# schematic.net
KiCad netlist of a schematic drawn in EAGLE
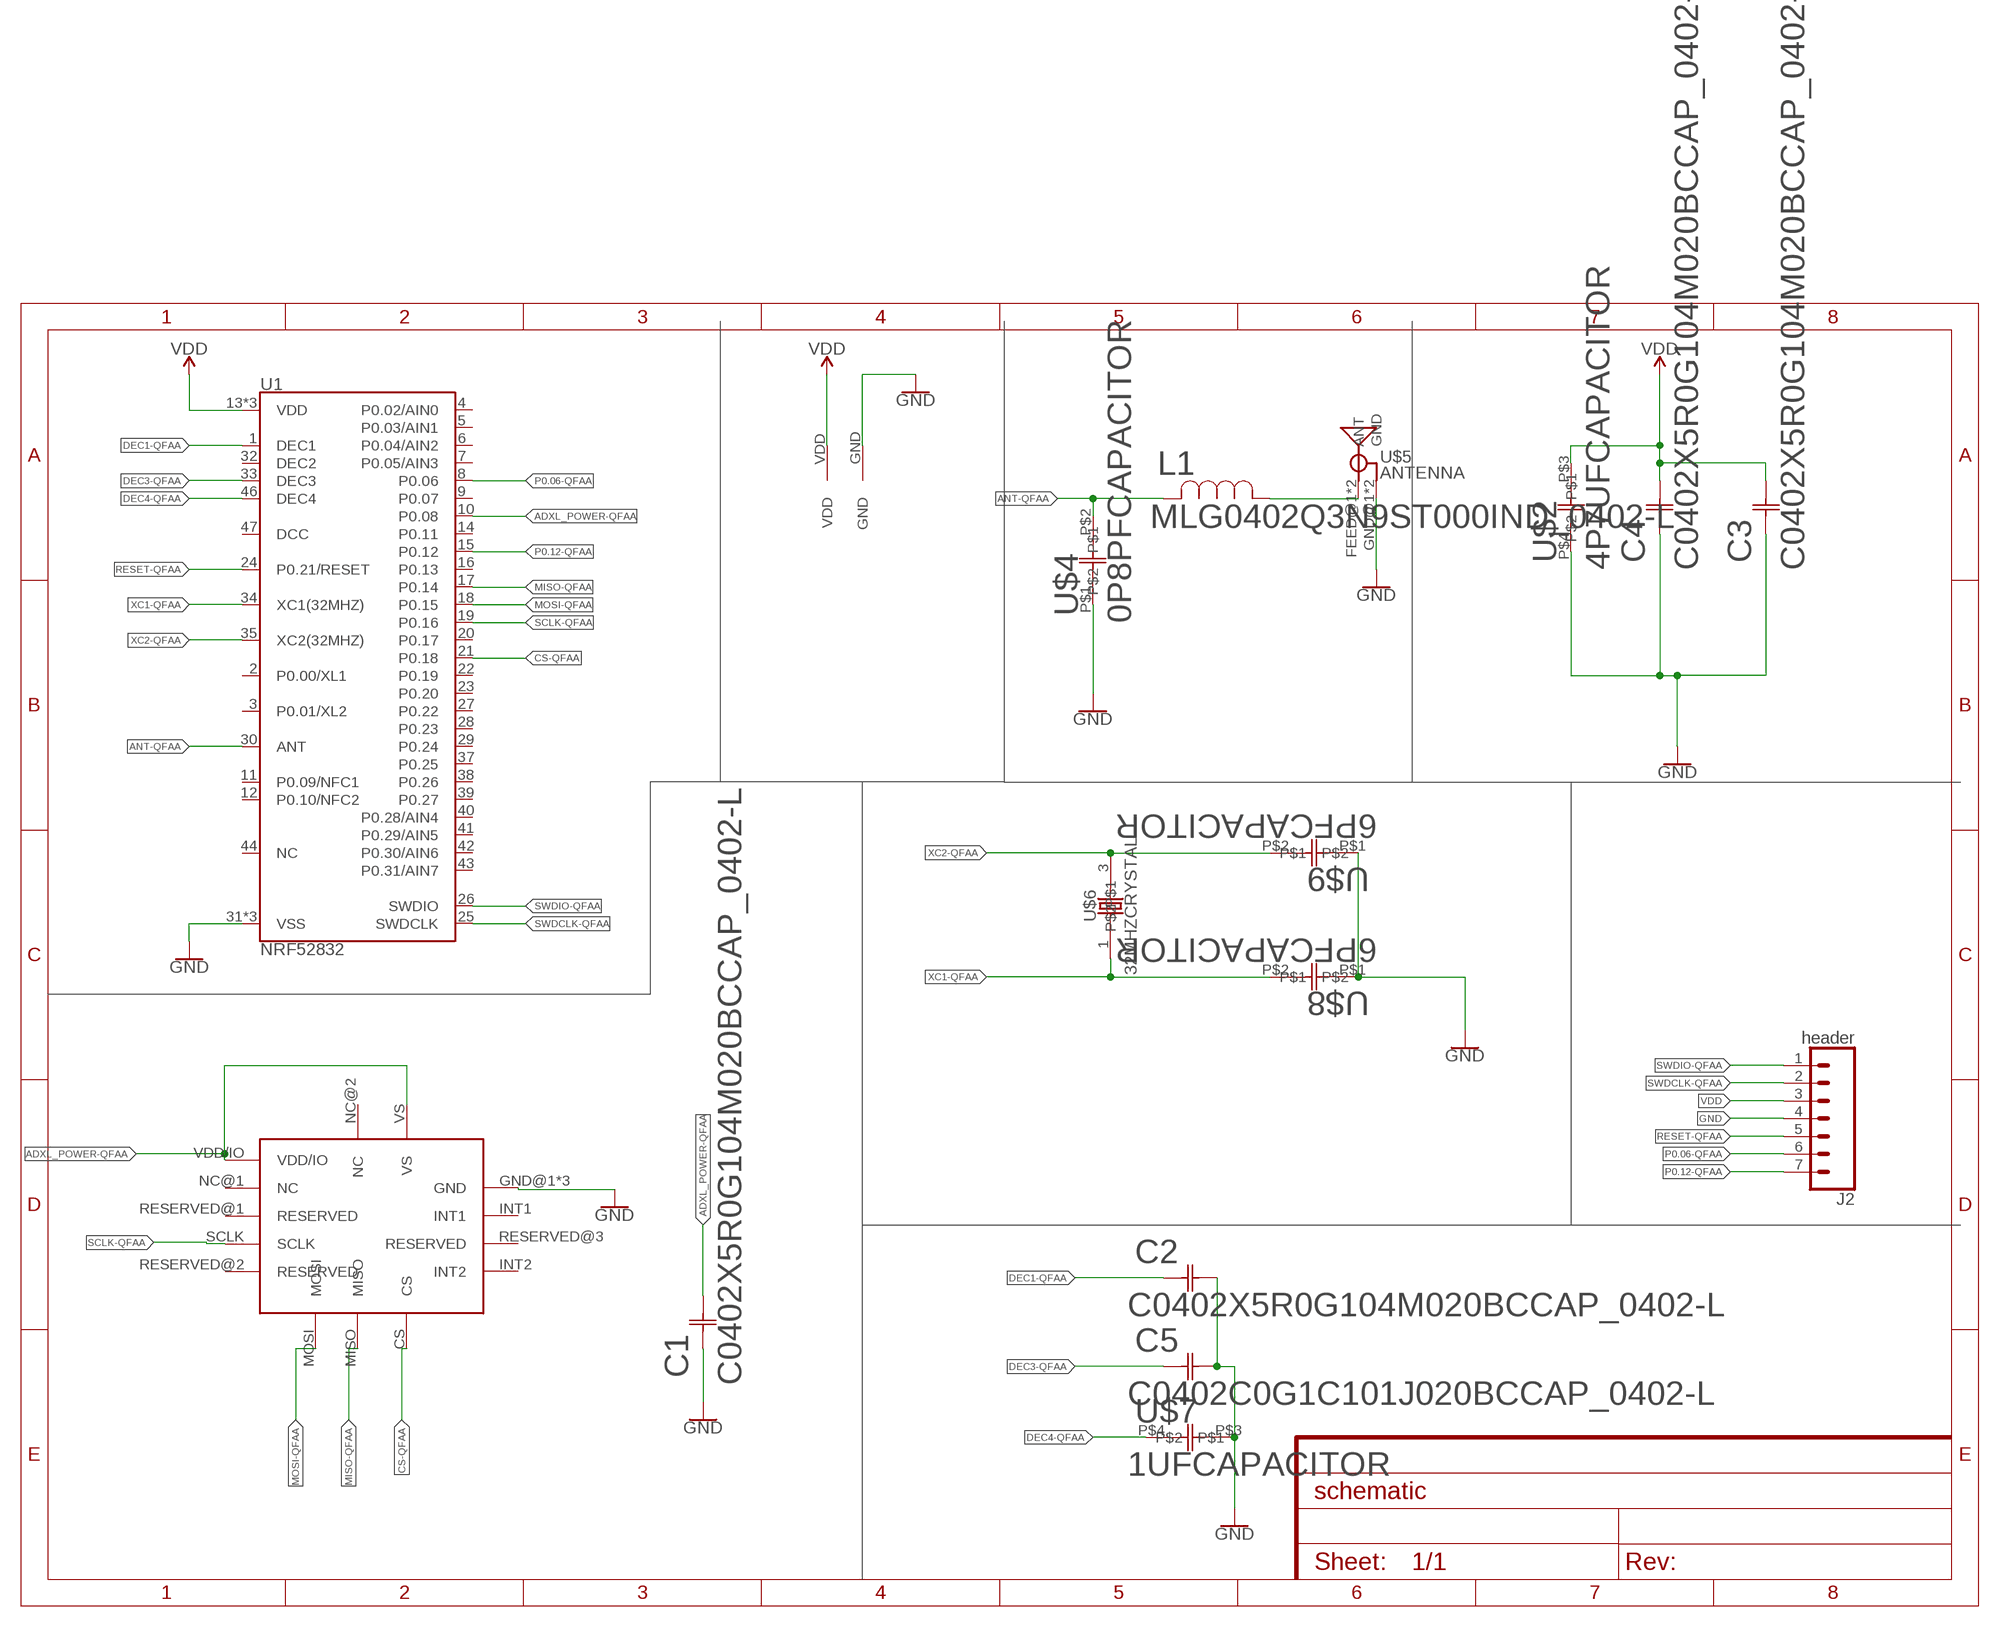
[diagram p0: schematic, sheet 1]

(export (version "E")
  (design (tool "Eeschema 10.0.6"))
  (components
    (comp (ref "C1")
      (value "C0402X5R0G104M020BCCAP_0402-L")
      (footprint "eagle-import:CAP_0402-L")
      (fields (field (name "MANUFACTURER_PART_NUMBER") "C0402C0G1C101J020BC"))
      (libsource (lib "eagle-import") (part "C0402X5R0G104M020BCCAP_0402-L"))
    )
    (comp (ref "C2")
      (value "C0402X5R0G104M020BCCAP_0402-L")
      (footprint "eagle-import:CAP_0402-L")
      (fields (field (name "MANUFACTURER_PART_NUMBER") "C0402C0G1C101J020BC"))
      (libsource (lib "eagle-import") (part "C0402X5R0G104M020BCCAP_0402-L"))
    )
    (comp (ref "C3")
      (value "C0402X5R0G104M020BCCAP_0402-L")
      (footprint "eagle-import:CAP_0402-L")
      (fields (field (name "MANUFACTURER_PART_NUMBER") "C0402C0G1C101J020BC"))
      (libsource (lib "eagle-import") (part "C0402X5R0G104M020BCCAP_0402-L"))
    )
    (comp (ref "C4")
      (value "C0402X5R0G104M020BCCAP_0402-L")
      (footprint "eagle-import:CAP_0402-L")
      (fields (field (name "MANUFACTURER_PART_NUMBER") "C0402C0G1C101J020BC"))
      (libsource (lib "eagle-import") (part "C0402X5R0G104M020BCCAP_0402-L"))
    )
    (comp (ref "C5")
      (value "C0402C0G1C101J020BCCAP_0402-L")
      (footprint "eagle-import:CAP_0402-L")
      (fields (field (name "MANUFACTURER_PART_NUMBER") "C0402C0G1C101J020BC"))
      (libsource (lib "eagle-import") (part "C0402C0G1C101J020BCCAP_0402-L"))
    )
    (comp (ref "J2")
      (value "header")
      (footprint "eagle-import:1X07")
      (libsource (lib "eagle-import") (part "CONN_07"))
    )
    (comp (ref "L1")
      (value "MLG0402Q3N9ST000IND_0402-L")
      (footprint "eagle-import:IND_0402-L")
      (fields (field (name "MANUFACTURER_PART_NUMBER") "MLG0402Q3N9ST000"))
      (libsource (lib "eagle-import") (part "MLG0402Q3N9ST000IND_0402-L"))
    )
    (comp (ref "U$1")
      (value "ADXL362")
      (footprint "eagle-import:TFLGA-16_3.3MMX3.1MM")
      (libsource (lib "eagle-import") (part "ADXL362"))
    )
    (comp (ref "U$2")
      (value "4P7UFCAPACITOR")
      (footprint "eagle-import:4P7UFCAPACITOR")
      (libsource (lib "eagle-import") (part "4P7UFCAPACITOR"))
    )
    (comp (ref "U$4")
      (value "0P8PFCAPACITOR")
      (footprint "eagle-import:0P8PFCAPACITOR")
      (libsource (lib "eagle-import") (part "0P8PFCAPACITOR"))
    )
    (comp (ref "U$5")
      (value "ANTENNA")
      (footprint "eagle-import:ANTENNA_FOOTPRINT")
      (libsource (lib "eagle-import") (part "ANTENNA"))
    )
    (comp (ref "U$6")
      (value "32MHZCRYSTAL")
      (footprint "eagle-import:32MHZCRYSTAL")
      (libsource (lib "eagle-import") (part "32MHZCRYSTAL"))
    )
    (comp (ref "U$7")
      (value "1UFCAPACITOR")
      (footprint "eagle-import:1UFCAPACITOR")
      (libsource (lib "eagle-import") (part "1UFCAPACITOR"))
    )
    (comp (ref "U$8")
      (value "6PFCAPACITOR")
      (footprint "eagle-import:6PFCAPACITOR")
      (libsource (lib "eagle-import") (part "6PFCAPACITOR"))
    )
    (comp (ref "U$9")
      (value "6PFCAPACITOR")
      (footprint "eagle-import:6PFCAPACITOR")
      (libsource (lib "eagle-import") (part "6PFCAPACITOR"))
    )
    (comp (ref "U$10")
      (value "POWER")
      (footprint "eagle-import:POWER")
      (libsource (lib "eagle-import") (part "POWER"))
    )
    (comp (ref "U1")
      (value "NRF52832")
      (footprint "eagle-import:QFN48-6X6MM")
      (libsource (lib "eagle-import") (part "NRF52832"))
    )
  )
  (nets
    (net (code "1") (name "ADXL_POWER-QFAA") (class "Default")
      (node (ref "C1") (pin "2") (pinfunction "22_2") (pintype "passive"))
      (node (ref "U$1") (pin "VDD/IO") (pinfunction "VDD/IO_VDD/IO") (pintype "bidirectional"))
      (node (ref "U$1") (pin "VS") (pinfunction "VS_VS") (pintype "bidirectional"))
      (node (ref "U1") (pin "10") (pinfunction "P0.08_10") (pintype "bidirectional"))
    )
    (net (code "2") (name "ANT-QFAA") (class "Default")
      (node (ref "L1") (pin "2") (pinfunction "2_2") (pintype "passive"))
      (node (ref "U$4") (pin "P$2") (pinfunction "P$2_P$2") (pintype "bidirectional"))
      (node (ref "U1") (pin "30") (pinfunction "ANT_30") (pintype "bidirectional"))
    )
    (net (code "3") (name "CS-QFAA") (class "Default")
      (node (ref "U$1") (pin "CS") (pinfunction "CS_CS") (pintype "bidirectional"))
      (node (ref "U1") (pin "21") (pinfunction "P0.18_21") (pintype "bidirectional"))
    )
    (net (code "4") (name "DEC1-QFAA") (class "Default")
      (node (ref "C2") (pin "1") (pinfunction "11_1") (pintype "passive"))
      (node (ref "U1") (pin "1") (pinfunction "DEC1_1") (pintype "bidirectional"))
    )
    (net (code "5") (name "DEC3-QFAA") (class "Default")
      (node (ref "C5") (pin "1") (pinfunction "11_1") (pintype "passive"))
      (node (ref "U1") (pin "33") (pinfunction "DEC3_33") (pintype "bidirectional"))
    )
    (net (code "6") (name "DEC4-QFAA") (class "Default")
      (node (ref "U$7") (pin "P$4") (pinfunction "P$1_P$4") (pintype "bidirectional"))
      (node (ref "U1") (pin "46") (pinfunction "DEC4_46") (pintype "bidirectional"))
    )
    (net (code "7") (name "GND") (class "Default")
      (node (ref "C1") (pin "1") (pinfunction "11_1") (pintype "passive"))
      (node (ref "C2") (pin "2") (pinfunction "22_2") (pintype "passive"))
      (node (ref "C3") (pin "1") (pinfunction "11_1") (pintype "passive"))
      (node (ref "C4") (pin "1") (pinfunction "11_1") (pintype "passive"))
      (node (ref "C5") (pin "2") (pinfunction "22_2") (pintype "passive"))
      (node (ref "J2") (pin "4") (pinfunction "4_4") (pintype "passive"))
      (node (ref "U$1") (pin "GND@1") (pinfunction "GND_GND@1") (pintype "bidirectional"))
      (node (ref "U$1") (pin "GND@2") (pinfunction "GND_GND@2") (pintype "bidirectional"))
      (node (ref "U$1") (pin "GND@3") (pinfunction "GND_GND@3") (pintype "bidirectional"))
      (node (ref "U$10") (pin "GND") (pinfunction "GND_GND") (pintype "bidirectional"))
      (node (ref "U$2") (pin "P$4") (pinfunction "P$1_P$4") (pintype "bidirectional"))
      (node (ref "U$4") (pin "P$1") (pinfunction "P$1_P$1") (pintype "bidirectional"))
      (node (ref "U$5") (pin "GND@1") (pinfunction "GND_GND@1") (pintype "bidirectional"))
      (node (ref "U$5") (pin "GND@2") (pinfunction "GND_GND@2") (pintype "bidirectional"))
      (node (ref "U$7") (pin "P$3") (pinfunction "P$2_P$3") (pintype "bidirectional"))
      (node (ref "U$8") (pin "P$1") (pinfunction "P$1_P$1") (pintype "bidirectional"))
      (node (ref "U$9") (pin "P$1") (pinfunction "P$1_P$1") (pintype "bidirectional"))
      (node (ref "U1") (pin "31") (pinfunction "VSS_31") (pintype "bidirectional"))
      (node (ref "U1") (pin "45") (pinfunction "VSS_45") (pintype "bidirectional"))
      (node (ref "U1") (pin "EP") (pinfunction "VSS_EP") (pintype "bidirectional"))
    )
    (net (code "8") (name "MISO-QFAA") (class "Default")
      (node (ref "U$1") (pin "MISO") (pinfunction "MISO_MISO") (pintype "bidirectional"))
      (node (ref "U1") (pin "17") (pinfunction "P0.14_17") (pintype "bidirectional"))
    )
    (net (code "9") (name "MOSI-QFAA") (class "Default")
      (node (ref "U$1") (pin "MOSI") (pinfunction "MOSI_MOSI") (pintype "bidirectional"))
      (node (ref "U1") (pin "18") (pinfunction "P0.15_18") (pintype "bidirectional"))
    )
    (net (code "10") (name "Net-(L1-Pad1)") (class "Default")
      (node (ref "L1") (pin "1") (pinfunction "1_1") (pintype "passive"))
      (node (ref "U$5") (pin "FEED@1") (pinfunction "ANT_FEED@1") (pintype "bidirectional"))
      (node (ref "U$5") (pin "FEED@2") (pinfunction "ANT_FEED@2") (pintype "bidirectional"))
    )
    (net (code "11") (name "P0.06-QFAA") (class "Default")
      (node (ref "J2") (pin "6") (pinfunction "6_6") (pintype "passive"))
      (node (ref "U1") (pin "8") (pinfunction "P0.06_8") (pintype "bidirectional"))
    )
    (net (code "12") (name "P0.12-QFAA") (class "Default")
      (node (ref "J2") (pin "7") (pinfunction "7_7") (pintype "passive"))
      (node (ref "U1") (pin "15") (pinfunction "P0.12_15") (pintype "bidirectional"))
    )
    (net (code "13") (name "RESET-QFAA") (class "Default")
      (node (ref "J2") (pin "5") (pinfunction "5_5") (pintype "passive"))
      (node (ref "U1") (pin "24") (pinfunction "P0.21/RESET_24") (pintype "bidirectional"))
    )
    (net (code "14") (name "SCLK-QFAA") (class "Default")
      (node (ref "U$1") (pin "SCLK") (pinfunction "SCLK_SCLK") (pintype "bidirectional"))
      (node (ref "U1") (pin "19") (pinfunction "P0.16_19") (pintype "bidirectional"))
    )
    (net (code "15") (name "SWDCLK-QFAA") (class "Default")
      (node (ref "J2") (pin "2") (pinfunction "2_2") (pintype "passive"))
      (node (ref "U1") (pin "25") (pinfunction "SWDCLK_25") (pintype "bidirectional"))
    )
    (net (code "16") (name "SWDIO-QFAA") (class "Default")
      (node (ref "J2") (pin "1") (pinfunction "1_1") (pintype "passive"))
      (node (ref "U1") (pin "26") (pinfunction "SWDIO_26") (pintype "bidirectional"))
    )
    (net (code "17") (name "VDD") (class "Default")
      (node (ref "C3") (pin "2") (pinfunction "22_2") (pintype "passive"))
      (node (ref "C4") (pin "2") (pinfunction "22_2") (pintype "passive"))
      (node (ref "J2") (pin "3") (pinfunction "3_3") (pintype "passive"))
      (node (ref "U$10") (pin "VDD") (pinfunction "VDD_VDD") (pintype "bidirectional"))
      (node (ref "U$2") (pin "P$3") (pinfunction "P$2_P$3") (pintype "bidirectional"))
      (node (ref "U1") (pin "13") (pinfunction "VDD_13") (pintype "bidirectional"))
      (node (ref "U1") (pin "36") (pinfunction "VDD_36") (pintype "bidirectional"))
      (node (ref "U1") (pin "48") (pinfunction "VDD_48") (pintype "bidirectional"))
    )
    (net (code "18") (name "XC1-QFAA") (class "Default")
      (node (ref "U$6") (pin "1") (pinfunction "P$1_1") (pintype "bidirectional"))
      (node (ref "U$8") (pin "P$2") (pinfunction "P$2_P$2") (pintype "bidirectional"))
      (node (ref "U1") (pin "34") (pinfunction "XC1(32MHZ)_34") (pintype "bidirectional"))
    )
    (net (code "19") (name "XC2-QFAA") (class "Default")
      (node (ref "U$6") (pin "3") (pinfunction "P$2_3") (pintype "bidirectional"))
      (node (ref "U$9") (pin "P$2") (pinfunction "P$2_P$2") (pintype "bidirectional"))
      (node (ref "U1") (pin "35") (pinfunction "XC2(32MHZ)_35") (pintype "bidirectional"))
    )
    (net (code "20") (name "unconnected-(U$1-NC-PadNC@1)") (class "Default")
      (node (ref "U$1") (pin "NC@1") (pinfunction "NC_NC@1") (pintype "bidirectional"))
    )
    (net (code "21") (name "unconnected-(U$1-NC-PadNC@2)") (class "Default")
      (node (ref "U$1") (pin "NC@2") (pinfunction "NC_NC@2") (pintype "bidirectional"))
    )
    (net (code "22") (name "unconnected-(U$1-PadINT1)") (class "Default")
      (node (ref "U$1") (pin "INT1") (pinfunction "INT1_INT1") (pintype "bidirectional"))
    )
    (net (code "23") (name "unconnected-(U$1-PadINT2)") (class "Default")
      (node (ref "U$1") (pin "INT2") (pinfunction "INT2_INT2") (pintype "bidirectional"))
    )
    (net (code "24") (name "unconnected-(U$1-RESERVED-PadRESERVED@1)") (class "Default")
      (node (ref "U$1") (pin "RESERVED@1") (pinfunction "RESERVED_RESERVED@1") (pintype "bidirectional"))
    )
    (net (code "25") (name "unconnected-(U$1-RESERVED-PadRESERVED@2)") (class "Default")
      (node (ref "U$1") (pin "RESERVED@2") (pinfunction "RESERVED_RESERVED@2") (pintype "bidirectional"))
    )
    (net (code "26") (name "unconnected-(U$1-RESERVED-PadRESERVED@3)") (class "Default")
      (node (ref "U$1") (pin "RESERVED@3") (pinfunction "RESERVED_RESERVED@3") (pintype "bidirectional"))
    )
    (net (code "27") (name "unconnected-(U1-DCC-Pad47)") (class "Default")
      (node (ref "U1") (pin "47") (pinfunction "DCC_47") (pintype "bidirectional"))
    )
    (net (code "28") (name "unconnected-(U1-DEC2-Pad32)") (class "Default")
      (node (ref "U1") (pin "32") (pinfunction "DEC2_32") (pintype "bidirectional"))
    )
    (net (code "29") (name "unconnected-(U1-NC-Pad44)") (class "Default")
      (node (ref "U1") (pin "44") (pinfunction "NC_44") (pintype "bidirectional"))
    )
    (net (code "30") (name "unconnected-(U1-P0.00{slash}XL1-Pad2)") (class "Default")
      (node (ref "U1") (pin "2") (pinfunction "P0.00/XL1_2") (pintype "bidirectional"))
    )
    (net (code "31") (name "unconnected-(U1-P0.01{slash}XL2-Pad3)") (class "Default")
      (node (ref "U1") (pin "3") (pinfunction "P0.01/XL2_3") (pintype "bidirectional"))
    )
    (net (code "32") (name "unconnected-(U1-P0.02{slash}AIN0-Pad4)") (class "Default")
      (node (ref "U1") (pin "4") (pinfunction "P0.02/AIN0_4") (pintype "bidirectional"))
    )
    (net (code "33") (name "unconnected-(U1-P0.03{slash}AIN1-Pad5)") (class "Default")
      (node (ref "U1") (pin "5") (pinfunction "P0.03/AIN1_5") (pintype "bidirectional"))
    )
    (net (code "34") (name "unconnected-(U1-P0.04{slash}AIN2-Pad6)") (class "Default")
      (node (ref "U1") (pin "6") (pinfunction "P0.04/AIN2_6") (pintype "bidirectional"))
    )
    (net (code "35") (name "unconnected-(U1-P0.05{slash}AIN3-Pad7)") (class "Default")
      (node (ref "U1") (pin "7") (pinfunction "P0.05/AIN3_7") (pintype "bidirectional"))
    )
    (net (code "36") (name "unconnected-(U1-P0.07-Pad9)") (class "Default")
      (node (ref "U1") (pin "9") (pinfunction "P0.07_9") (pintype "bidirectional"))
    )
    (net (code "37") (name "unconnected-(U1-P0.09{slash}NFC1-Pad11)") (class "Default")
      (node (ref "U1") (pin "11") (pinfunction "P0.09/NFC1_11") (pintype "bidirectional"))
    )
    (net (code "38") (name "unconnected-(U1-P0.10{slash}NFC2-Pad12)") (class "Default")
      (node (ref "U1") (pin "12") (pinfunction "P0.10/NFC2_12") (pintype "bidirectional"))
    )
    (net (code "39") (name "unconnected-(U1-P0.11-Pad14)") (class "Default")
      (node (ref "U1") (pin "14") (pinfunction "P0.11_14") (pintype "bidirectional"))
    )
    (net (code "40") (name "unconnected-(U1-P0.13-Pad16)") (class "Default")
      (node (ref "U1") (pin "16") (pinfunction "P0.13_16") (pintype "bidirectional"))
    )
    (net (code "41") (name "unconnected-(U1-P0.17-Pad20)") (class "Default")
      (node (ref "U1") (pin "20") (pinfunction "P0.17_20") (pintype "bidirectional"))
    )
    (net (code "42") (name "unconnected-(U1-P0.19-Pad22)") (class "Default")
      (node (ref "U1") (pin "22") (pinfunction "P0.19_22") (pintype "bidirectional"))
    )
    (net (code "43") (name "unconnected-(U1-P0.20-Pad23)") (class "Default")
      (node (ref "U1") (pin "23") (pinfunction "P0.20_23") (pintype "bidirectional"))
    )
    (net (code "44") (name "unconnected-(U1-P0.22-Pad27)") (class "Default")
      (node (ref "U1") (pin "27") (pinfunction "P0.22_27") (pintype "bidirectional"))
    )
    (net (code "45") (name "unconnected-(U1-P0.23-Pad28)") (class "Default")
      (node (ref "U1") (pin "28") (pinfunction "P0.23_28") (pintype "bidirectional"))
    )
    (net (code "46") (name "unconnected-(U1-P0.24-Pad29)") (class "Default")
      (node (ref "U1") (pin "29") (pinfunction "P0.24_29") (pintype "bidirectional"))
    )
    (net (code "47") (name "unconnected-(U1-P0.25-Pad37)") (class "Default")
      (node (ref "U1") (pin "37") (pinfunction "P0.25_37") (pintype "bidirectional"))
    )
    (net (code "48") (name "unconnected-(U1-P0.26-Pad38)") (class "Default")
      (node (ref "U1") (pin "38") (pinfunction "P0.26_38") (pintype "bidirectional"))
    )
    (net (code "49") (name "unconnected-(U1-P0.27-Pad39)") (class "Default")
      (node (ref "U1") (pin "39") (pinfunction "P0.27_39") (pintype "bidirectional"))
    )
    (net (code "50") (name "unconnected-(U1-P0.28{slash}AIN4-Pad40)") (class "Default")
      (node (ref "U1") (pin "40") (pinfunction "P0.28/AIN4_40") (pintype "bidirectional"))
    )
    (net (code "51") (name "unconnected-(U1-P0.29{slash}AIN5-Pad41)") (class "Default")
      (node (ref "U1") (pin "41") (pinfunction "P0.29/AIN5_41") (pintype "bidirectional"))
    )
    (net (code "52") (name "unconnected-(U1-P0.30{slash}AIN6-Pad42)") (class "Default")
      (node (ref "U1") (pin "42") (pinfunction "P0.30/AIN6_42") (pintype "bidirectional"))
    )
    (net (code "53") (name "unconnected-(U1-P0.31{slash}AIN7-Pad43)") (class "Default")
      (node (ref "U1") (pin "43") (pinfunction "P0.31/AIN7_43") (pintype "bidirectional"))
    )
  )
)
